# USB_Circuit.net
KiCad netlist of a schematic drawn in Altium Designer
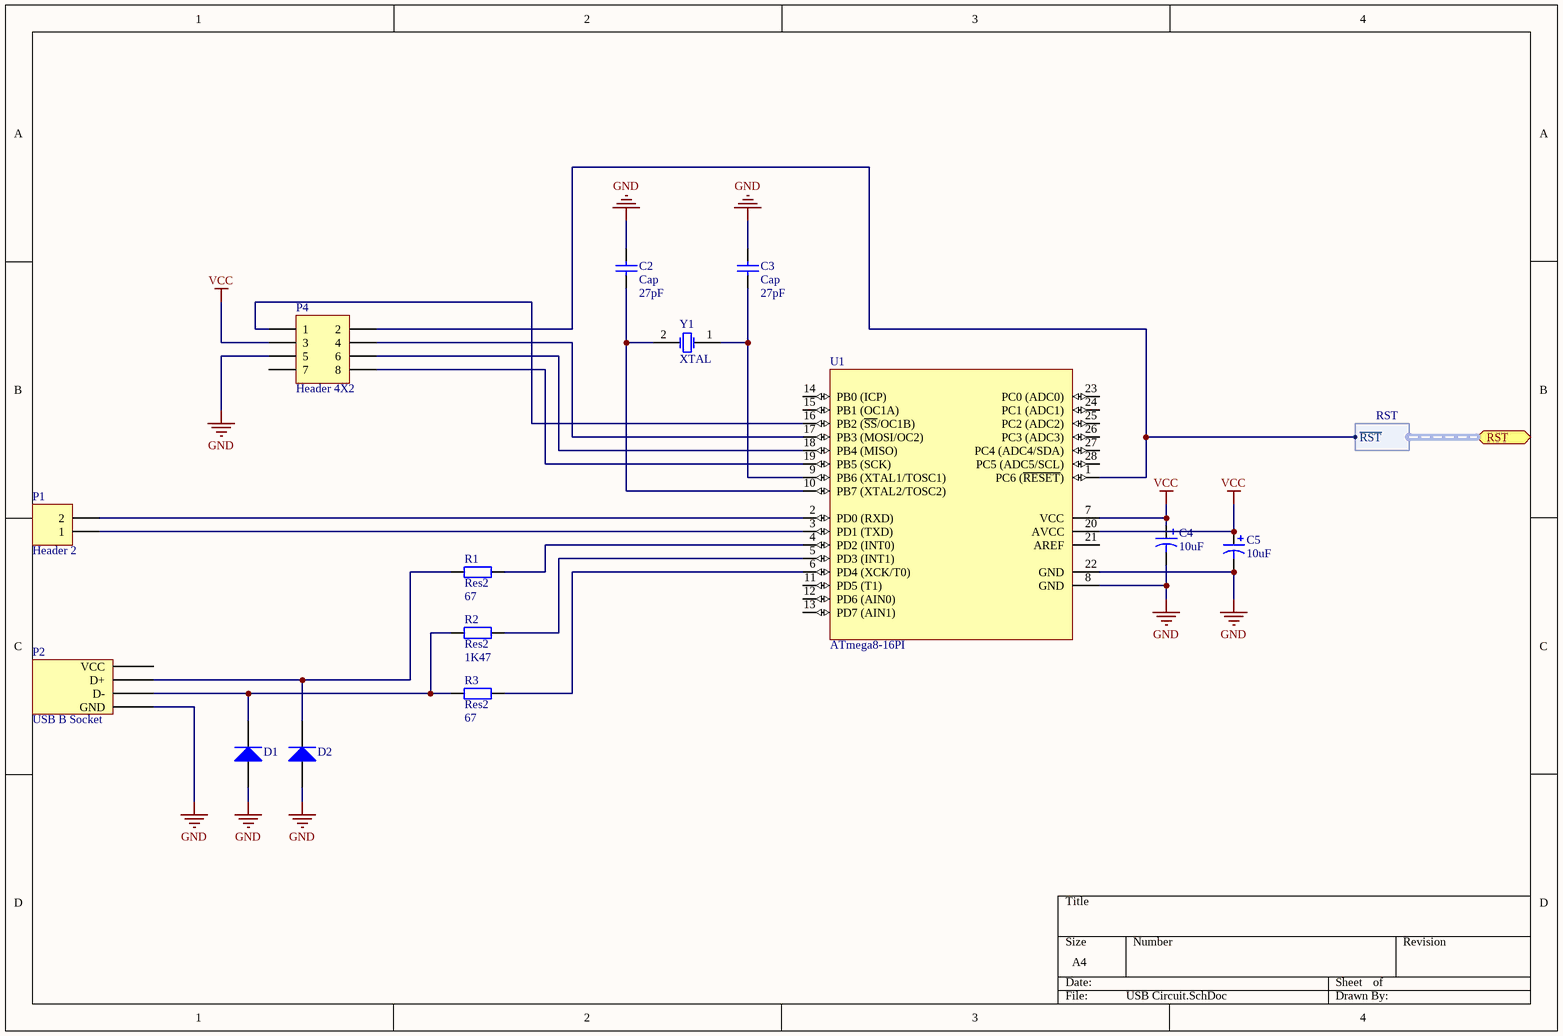
[diagram p0: USB Circuit.SchDoc]

(export (version "E")
  (design (tool "Eeschema 10.0.6"))
  (components
    (comp (ref "C2")
      (value "Cap")
      (footprint "CAPR2.54-5.1x3.2")
      (description "Capacitor")
      (fields (field (name "ALTIUM_VALUE") "27pF") (field (name "PUBLISHER") "Altium Limited"))
      (libsource (lib "Miscellaneous Devices") (part "Cap"))
    )
    (comp (ref "C3")
      (value "Cap")
      (footprint "CAPR2.54-5.1x3.2")
      (description "Capacitor")
      (fields (field (name "ALTIUM_VALUE") "27pF") (field (name "PUBLISHER") "Altium Limited"))
      (libsource (lib "Miscellaneous Devices") (part "Cap"))
    )
    (comp (ref "C4")
      (value "10uF")
      (footprint "CAPPR1.5-4x5")
      (description "Polarized Capacitor (Radial)")
      (fields (field (name "Comment") "Cap Pol1") (field (name "PUBLISHER") "Altium Limited"))
      (libsource (lib "Miscellaneous Devices") (part "Cap Pol1"))
    )
    (comp (ref "C5")
      (value "10uF")
      (footprint "CAPPR1.5-4x5")
      (description "Polarized Capacitor (Radial)")
      (fields (field (name "Comment") "Cap Pol1") (field (name "PUBLISHER") "Altium Limited"))
      (libsource (lib "Miscellaneous Devices") (part "Cap Pol1"))
    )
    (comp (ref "D1")
      (value "BZX79-C3V6")
      (footprint "SOD27")
      (description "Voltage Regulator Diode")
      (fields (field (name "PUBLISHER") "Altium Limited"))
      (libsource (lib "Philips Discrete Diode - Switching") (part "BZX79-C3V6"))
    )
    (comp (ref "D2")
      (value "BZX79-C3V6")
      (footprint "SOD27")
      (description "Voltage Regulator Diode")
      (fields (field (name "PUBLISHER") "Altium Limited"))
      (libsource (lib "Philips Discrete Diode - Switching") (part "BZX79-C3V6"))
    )
    (comp (ref "P1")
      (value "Header 2")
      (footprint "HDR1X2")
      (description "Header, 2-Pin")
      (fields (field (name "PUBLISHER") "Altium Limited"))
      (libsource (lib "Miscellaneous Connectors") (part "Header 2"))
    )
    (comp (ref "P2")
      (value "USB B Socket")
      (footprint "Components:USB B Socket")
      (libsource (lib "Components") (part "USB B Socket"))
    )
    (comp (ref "P4")
      (value "Header 4X2")
      (footprint "HDR2X4")
      (description "Header, 4-Pin, Dual row")
      (fields (field (name "PUBLISHER") "Altium Limited"))
      (libsource (lib "Miscellaneous Connectors") (part "Header 4X2"))
    )
    (comp (ref "R1")
      (value "Res2")
      (footprint "AXIAL-0.4")
      (description "Resistor")
      (fields (field (name "ALTIUM_VALUE") "67") (field (name "PUBLISHER") "Altium Limited"))
      (libsource (lib "") (part "Res2_1"))
    )
    (comp (ref "R2")
      (value "Res2")
      (footprint "AXIAL-0.4")
      (description "Resistor")
      (fields (field (name "ALTIUM_VALUE") "1K47") (field (name "PUBLISHER") "Altium Limited"))
      (libsource (lib "Miscellaneous Devices") (part "Res2"))
    )
    (comp (ref "R3")
      (value "Res2")
      (footprint "AXIAL-0.4")
      (description "Resistor")
      (fields (field (name "ALTIUM_VALUE") "67") (field (name "PUBLISHER") "Altium Limited"))
      (libsource (lib "") (part "Res2_1"))
    )
    (comp (ref "U1")
      (value "ATmega8-16PI")
      (footprint "28P3")
      (description "8-Bit AVR Microcontroller with 8K Bytes of In-System Programmable Flash Memory")
      (fields (field (name "PUBLISHER") "Altium Limited"))
      (libsource (lib "Atmel Microcontroller 8-Bit AVR") (part "ATmega8-16PI"))
    )
    (comp (ref "Y1")
      (value "XTAL")
      (footprint "Crystal Oscillator")
      (libsource (lib "Components") (part "Crystal Oscillator"))
    )
  )
  (nets
    (net (code "3") (name "GND") (class "Default")
      (node (ref "C2") (pin "2") (pinfunction "2_2") (pintype "passive"))
      (node (ref "C3") (pin "2") (pinfunction "2_2") (pintype "passive"))
      (node (ref "C4") (pin "2") (pinfunction "2_2") (pintype "passive"))
      (node (ref "C5") (pin "2") (pinfunction "2_2") (pintype "passive"))
      (node (ref "D1") (pin "1") (pinfunction "A_1") (pintype "passive"))
      (node (ref "D2") (pin "1") (pinfunction "A_1") (pintype "passive"))
      (node (ref "P2") (pin "GND") (pinfunction "GND_GND") (pintype "passive"))
      (node (ref "P4") (pin "5") (pinfunction "5_5") (pintype "passive"))
      (node (ref "U1") (pin "22") (pinfunction "GND_22") (pintype "power_in"))
      (node (ref "U1") (pin "8") (pinfunction "GND_8") (pintype "power_in"))
    )
    (net (code "4") (name "Net-(D1-K)") (class "Default")
      (node (ref "D1") (pin "2") (pinfunction "K_2") (pintype "passive"))
      (node (ref "P2") (pin "D-") (pinfunction "D-_D-") (pintype "passive"))
      (node (ref "R2") (pin "2") (pinfunction "2_2") (pintype "passive"))
      (node (ref "R3") (pin "1") (pinfunction "1_1") (pintype "passive"))
    )
    (net (code "5") (name "Net-(D2-K)") (class "Default")
      (node (ref "D2") (pin "2") (pinfunction "K_2") (pintype "passive"))
      (node (ref "P2") (pin "D+") (pinfunction "D+_D+") (pintype "passive"))
      (node (ref "R1") (pin "1") (pinfunction "1_1") (pintype "passive"))
    )
    (net (code "6") (name "Net-(U1-PB2_(~{SS}{slash}OC1B))") (class "Default")
      (node (ref "P4") (pin "1") (pinfunction "1_1") (pintype "passive"))
      (node (ref "U1") (pin "16") (pinfunction "PB2_(~{SS}/OC1B)_16") (pintype "bidirectional"))
    )
    (net (code "7") (name "Net-(U1-PB3_(MOSI{slash}OC2))") (class "Default")
      (node (ref "P4") (pin "4") (pinfunction "4_4") (pintype "passive"))
      (node (ref "U1") (pin "17") (pinfunction "PB3_(MOSI/OC2)_17") (pintype "bidirectional"))
    )
    (net (code "8") (name "Net-(U1-PB4_(MISO))") (class "Default")
      (node (ref "P4") (pin "6") (pinfunction "6_6") (pintype "passive"))
      (node (ref "U1") (pin "18") (pinfunction "PB4_(MISO)_18") (pintype "bidirectional"))
    )
    (net (code "9") (name "Net-(U1-PB5_(SCK))") (class "Default")
      (node (ref "P4") (pin "8") (pinfunction "8_8") (pintype "passive"))
      (node (ref "U1") (pin "19") (pinfunction "PB5_(SCK)_19") (pintype "bidirectional"))
    )
    (net (code "10") (name "Net-(U1-PB6_(XTAL1{slash}TOSC1))") (class "Default")
      (node (ref "C3") (pin "1") (pinfunction "1_1") (pintype "passive"))
      (node (ref "U1") (pin "9") (pinfunction "PB6_(XTAL1/TOSC1)_9") (pintype "bidirectional"))
      (node (ref "Y1") (pin "1") (pinfunction "OSC1_1") (pintype "passive"))
    )
    (net (code "11") (name "Net-(U1-PB7_(XTAL2{slash}TOSC2))") (class "Default")
      (node (ref "C2") (pin "1") (pinfunction "1_1") (pintype "passive"))
      (node (ref "U1") (pin "10") (pinfunction "PB7_(XTAL2/TOSC2)_10") (pintype "bidirectional"))
      (node (ref "Y1") (pin "2") (pinfunction "OSC2_2") (pintype "passive"))
    )
    (net (code "12") (name "Net-(U1-PC6_(~{RESET}))") (class "Default")
      (node (ref "P4") (pin "2") (pinfunction "2_2") (pintype "passive"))
      (node (ref "U1") (pin "1") (pinfunction "PC6_(~{RESET})_1") (pintype "bidirectional"))
    )
    (net (code "13") (name "Net-(U1-PD0_(RXD))") (class "Default")
      (node (ref "P1") (pin "2") (pinfunction "2_2") (pintype "passive"))
      (node (ref "U1") (pin "2") (pinfunction "PD0_(RXD)_2") (pintype "bidirectional"))
    )
    (net (code "14") (name "Net-(U1-PD1_(TXD))") (class "Default")
      (node (ref "P1") (pin "1") (pinfunction "1_1") (pintype "passive"))
      (node (ref "U1") (pin "3") (pinfunction "PD1_(TXD)_3") (pintype "bidirectional"))
    )
    (net (code "15") (name "Net-(U1-PD2_(INT0))") (class "Default")
      (node (ref "R1") (pin "2") (pinfunction "2_2") (pintype "passive"))
      (node (ref "U1") (pin "4") (pinfunction "PD2_(INT0)_4") (pintype "bidirectional"))
    )
    (net (code "16") (name "Net-(U1-PD3_(INT1))") (class "Default")
      (node (ref "R2") (pin "1") (pinfunction "1_1") (pintype "passive"))
      (node (ref "U1") (pin "5") (pinfunction "PD3_(INT1)_5") (pintype "bidirectional"))
    )
    (net (code "17") (name "Net-(U1-PD4_(XCK{slash}T0))") (class "Default")
      (node (ref "R3") (pin "2") (pinfunction "2_2") (pintype "passive"))
      (node (ref "U1") (pin "6") (pinfunction "PD4_(XCK/T0)_6") (pintype "bidirectional"))
    )
    (net (code "18") (name "VCC") (class "Default")
      (node (ref "C4") (pin "1") (pinfunction "1_1") (pintype "passive"))
      (node (ref "C5") (pin "1") (pinfunction "1_1") (pintype "passive"))
      (node (ref "P4") (pin "3") (pinfunction "3_3") (pintype "passive"))
      (node (ref "U1") (pin "20") (pinfunction "AVCC_20") (pintype "power_in"))
      (node (ref "U1") (pin "7") (pinfunction "VCC_7") (pintype "power_in"))
    )
    (net (code "19") (name "unconnected-(P2-PadVCC)") (class "Default")
      (node (ref "P2") (pin "VCC") (pinfunction "VCC_VCC") (pintype "passive"))
    )
    (net (code "20") (name "unconnected-(P4-Pad7)") (class "Default")
      (node (ref "P4") (pin "7") (pinfunction "7_7") (pintype "passive"))
    )
    (net (code "21") (name "unconnected-(U1-AREF-Pad21)") (class "Default")
      (node (ref "U1") (pin "21") (pinfunction "AREF_21") (pintype "passive"))
    )
    (net (code "22") (name "unconnected-(U1-PB0_(ICP)-Pad14)") (class "Default")
      (node (ref "U1") (pin "14") (pinfunction "PB0_(ICP)_14") (pintype "bidirectional"))
    )
    (net (code "23") (name "unconnected-(U1-PB1_(OC1A)-Pad15)") (class "Default")
      (node (ref "U1") (pin "15") (pinfunction "PB1_(OC1A)_15") (pintype "bidirectional"))
    )
    (net (code "24") (name "unconnected-(U1-PC0_(ADC0)-Pad23)") (class "Default")
      (node (ref "U1") (pin "23") (pinfunction "PC0_(ADC0)_23") (pintype "bidirectional"))
    )
    (net (code "25") (name "unconnected-(U1-PC1_(ADC1)-Pad24)") (class "Default")
      (node (ref "U1") (pin "24") (pinfunction "PC1_(ADC1)_24") (pintype "bidirectional"))
    )
    (net (code "26") (name "unconnected-(U1-PC2_(ADC2)-Pad25)") (class "Default")
      (node (ref "U1") (pin "25") (pinfunction "PC2_(ADC2)_25") (pintype "bidirectional"))
    )
    (net (code "27") (name "unconnected-(U1-PC3_(ADC3)-Pad26)") (class "Default")
      (node (ref "U1") (pin "26") (pinfunction "PC3_(ADC3)_26") (pintype "bidirectional"))
    )
    (net (code "28") (name "unconnected-(U1-PC4_(ADC4{slash}SDA)-Pad27)") (class "Default")
      (node (ref "U1") (pin "27") (pinfunction "PC4_(ADC4/SDA)_27") (pintype "bidirectional"))
    )
    (net (code "29") (name "unconnected-(U1-PC5_(ADC5{slash}SCL)-Pad28)") (class "Default")
      (node (ref "U1") (pin "28") (pinfunction "PC5_(ADC5/SCL)_28") (pintype "bidirectional"))
    )
    (net (code "30") (name "unconnected-(U1-PD5_(T1)-Pad11)") (class "Default")
      (node (ref "U1") (pin "11") (pinfunction "PD5_(T1)_11") (pintype "bidirectional"))
    )
    (net (code "31") (name "unconnected-(U1-PD6_(AIN0)-Pad12)") (class "Default")
      (node (ref "U1") (pin "12") (pinfunction "PD6_(AIN0)_12") (pintype "bidirectional"))
    )
    (net (code "32") (name "unconnected-(U1-PD7_(AIN1)-Pad13)") (class "Default")
      (node (ref "U1") (pin "13") (pinfunction "PD7_(AIN1)_13") (pintype "bidirectional"))
    )
  )
)
